# FingerTip.net
KiCad netlist of a schematic drawn in Altium Designer
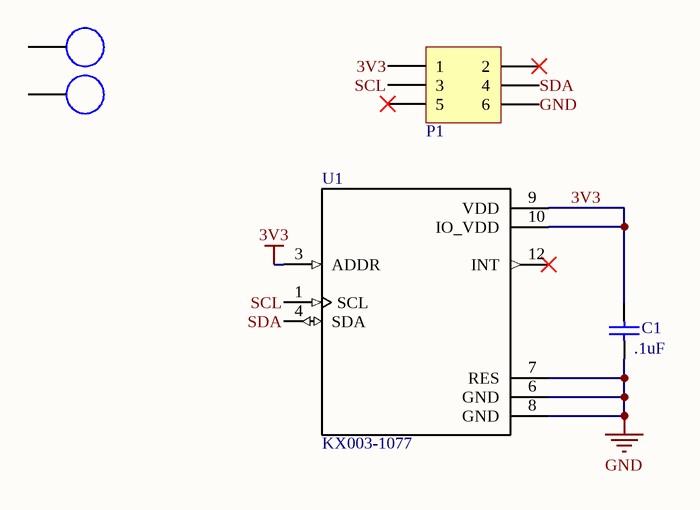
[diagram p0: FingerTip.SchDoc]

(export (version "E")
  (design (tool "Eeschema 10.0.6"))
  (components
    (comp (ref "C1")
      (value ".1uF")
      (footprint "0805")
      (description ".1, 10%, 50V")
      (fields (field (name "GFUPARTNO") "CL21A475KPFNNNE"))
      (libsource (lib "AltiumGFU64") (part "Cap"))
    )
    (comp (ref "DR3")
      (value "4-40 DRILL HOLE")
      (footprint "4_40 DRILL HOLE")
      (description "Mounting hole for 4-40 screw, non-BOM")
      (fields (field (name "GFUPARTNO") "4_40 DRILL HOLE"))
      (libsource (lib "AltiumGFU64") (part "8_32 DRILL HOLE"))
    )
    (comp (ref "DR4")
      (value "4-40 DRILL HOLE")
      (footprint "4_40 DRILL HOLE")
      (description "Mounting hole for 4-40 screw, non-BOM")
      (fields (field (name "GFUPARTNO") "4_40 DRILL HOLE"))
      (libsource (lib "AltiumGFU64") (part "8_32 DRILL HOLE"))
    )
    (comp (ref "P1")
      (value "90131-0123")
      (footprint "HDR2X3")
      (description "MOLEX CONN HEADER 6POS 2ROW .100\" STR TIN")
      (libsource (lib "AltiumGFU64") (part "Header 3X2"))
    )
    (comp (ref "U1")
      (value "KX003-1077")
      (footprint "*XDCR_KX003-1077")
      (description "Accelerometer X, Y, Z Axis Â±2g, 4g, 8g, 16g 3.5kHz _X,Y_, 1.8kHz _Z_ 12-LGA _2x2_")
      (fields
        (field (name "DIGI-KEY_PART_NUMBER") "KX003-1077CT-ND")
        (field (name "MF") "Rohm Semiconductor")
      )
      (libsource (lib "KX003-1077") (part "KX003-1077"))
    )
  )
  (nets
    (net (code "1") (name "/SCL") (class "Default")
      (node (ref "P1") (pin "3") (pinfunction "3_3") (pintype "passive"))
      (node (ref "U1") (pin "1") (pinfunction "SCL_1") (pintype "input"))
    )
    (net (code "2") (name "/SDA") (class "Default")
      (node (ref "P1") (pin "4") (pinfunction "4_4") (pintype "passive"))
      (node (ref "U1") (pin "4") (pinfunction "SDA_4") (pintype "bidirectional"))
    )
    (net (code "3") (name "3V3") (class "Default")
      (node (ref "C1") (pin "2") (pinfunction "2_2") (pintype "passive"))
      (node (ref "P1") (pin "1") (pinfunction "1_1") (pintype "passive"))
      (node (ref "U1") (pin "10") (pinfunction "IO_VDD_10") (pintype "power_in"))
      (node (ref "U1") (pin "3") (pinfunction "ADDR_3") (pintype "input"))
      (node (ref "U1") (pin "9") (pinfunction "VDD_9") (pintype "power_in"))
    )
    (net (code "4") (name "GND") (class "Default")
      (node (ref "C1") (pin "1") (pinfunction "1_1") (pintype "passive"))
      (node (ref "P1") (pin "6") (pinfunction "6_6") (pintype "passive"))
      (node (ref "U1") (pin "6") (pinfunction "GND_6") (pintype "power_in"))
      (node (ref "U1") (pin "7") (pinfunction "RES_7") (pintype "power_in"))
      (node (ref "U1") (pin "8") (pinfunction "GND_8") (pintype "power_in"))
    )
    (net (code "5") (name "unconnected-(DR3-Pad0)") (class "Default")
      (node (ref "DR3") (pin "0") (pinfunction "0_0") (pintype "passive"))
    )
    (net (code "6") (name "unconnected-(DR4-Pad0)") (class "Default")
      (node (ref "DR4") (pin "0") (pinfunction "0_0") (pintype "passive"))
    )
    (net (code "7") (name "unconnected-(P1-Pad2)") (class "Default")
      (node (ref "P1") (pin "2") (pinfunction "2_2") (pintype "passive+no_connect"))
    )
    (net (code "8") (name "unconnected-(P1-Pad5)") (class "Default")
      (node (ref "P1") (pin "5") (pinfunction "5_5") (pintype "passive+no_connect"))
    )
    (net (code "9") (name "unconnected-(U1-INT-Pad12)") (class "Default")
      (node (ref "U1") (pin "12") (pinfunction "INT_12") (pintype "output+no_connect"))
    )
  )
)
